# VibeMotors.net
KiCad netlist of a schematic drawn in EAGLE
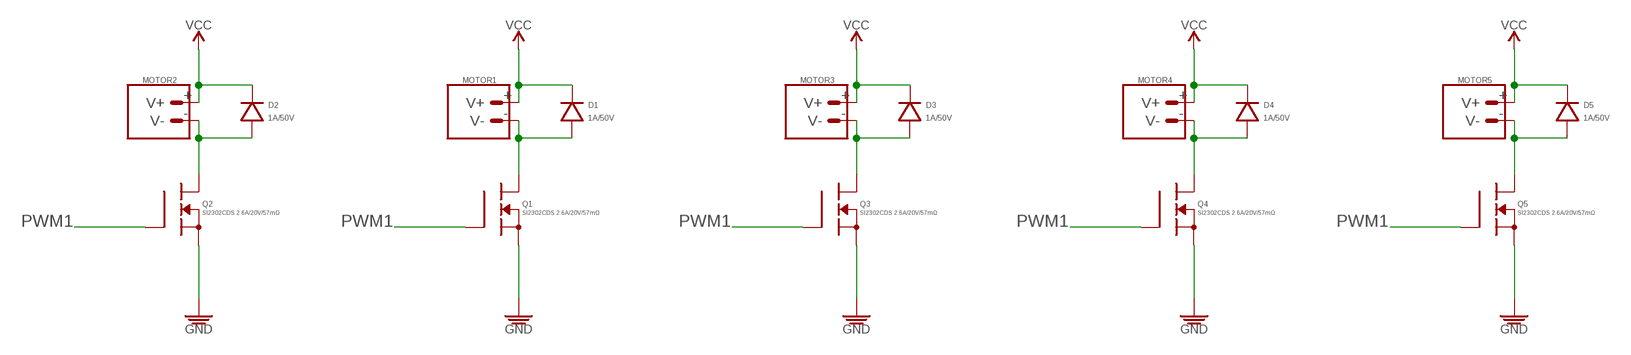
[diagram p0: schematic, sheet 1]

(export (version "E")
  (design (tool "Eeschema 10.0.6"))
  (components
    (comp (ref "D1")
      (value "1A/50V")
      (footprint "eagle-import:SOD123F")
      (fields
        (field (name "MFR") "Comchip Technology")
        (field (name "MPN") "CGRKM4001-HF")
        (field (name "CREATOR") "MrSwirlyEyes")
      )
      (libsource (lib "eagle-import") (part "DIODE_GENERAL-PURPOSE_SMD_GP_1A-50V"))
    )
    (comp (ref "D2")
      (value "1A/50V")
      (footprint "eagle-import:SOD123F")
      (fields
        (field (name "MFR") "Comchip Technology")
        (field (name "MPN") "CGRKM4001-HF")
        (field (name "CREATOR") "MrSwirlyEyes")
      )
      (libsource (lib "eagle-import") (part "DIODE_GENERAL-PURPOSE_SMD_GP_1A-50V"))
    )
    (comp (ref "D3")
      (value "1A/50V")
      (footprint "eagle-import:SOD123F")
      (fields
        (field (name "MFR") "Comchip Technology")
        (field (name "MPN") "CGRKM4001-HF")
        (field (name "CREATOR") "MrSwirlyEyes")
      )
      (libsource (lib "eagle-import") (part "DIODE_GENERAL-PURPOSE_SMD_GP_1A-50V"))
    )
    (comp (ref "D4")
      (value "1A/50V")
      (footprint "eagle-import:SOD123F")
      (fields
        (field (name "MFR") "Comchip Technology")
        (field (name "MPN") "CGRKM4001-HF")
        (field (name "CREATOR") "MrSwirlyEyes")
      )
      (libsource (lib "eagle-import") (part "DIODE_GENERAL-PURPOSE_SMD_GP_1A-50V"))
    )
    (comp (ref "D5")
      (value "1A/50V")
      (footprint "eagle-import:SOD123F")
      (fields
        (field (name "MFR") "Comchip Technology")
        (field (name "MPN") "CGRKM4001-HF")
        (field (name "CREATOR") "MrSwirlyEyes")
      )
      (libsource (lib "eagle-import") (part "DIODE_GENERAL-PURPOSE_SMD_GP_1A-50V"))
    )
    (comp (ref "MOTOR1")
      (value "MOTOR_PADSPTH")
      (footprint "eagle-import:CONNECTOR_MOTOR")
      (libsource (lib "eagle-import") (part "MOTOR_PADSPTH"))
    )
    (comp (ref "MOTOR2")
      (value "MOTOR_PADSPTH")
      (footprint "eagle-import:CONNECTOR_MOTOR")
      (libsource (lib "eagle-import") (part "MOTOR_PADSPTH"))
    )
    (comp (ref "MOTOR3")
      (value "MOTOR_PADSPTH")
      (footprint "eagle-import:CONNECTOR_MOTOR")
      (libsource (lib "eagle-import") (part "MOTOR_PADSPTH"))
    )
    (comp (ref "MOTOR4")
      (value "MOTOR_PADSPTH")
      (footprint "eagle-import:CONNECTOR_MOTOR")
      (libsource (lib "eagle-import") (part "MOTOR_PADSPTH"))
    )
    (comp (ref "MOTOR5")
      (value "MOTOR_PADSPTH")
      (footprint "eagle-import:CONNECTOR_MOTOR")
      (libsource (lib "eagle-import") (part "MOTOR_PADSPTH"))
    )
    (comp (ref "Q1")
      (value "SI2302CDS 2.6A/20V/57mΩ")
      (footprint "eagle-import:SOT23-3")
      (fields
        (field (name "MFR") "Vishay Siliconix")
        (field (name "MPN") "SI2302CDS-T1-GE3")
        (field (name "CREATOR") "MrSwirlyEyes")
      )
      (libsource (lib "eagle-import") (part "MOSFET_N-CHANNEL_SI2302CDS_2.6A-20V-0.057OHM"))
    )
    (comp (ref "Q2")
      (value "SI2302CDS 2.6A/20V/57mΩ")
      (footprint "eagle-import:SOT23-3")
      (fields
        (field (name "MFR") "Vishay Siliconix")
        (field (name "MPN") "SI2302CDS-T1-GE3")
        (field (name "CREATOR") "MrSwirlyEyes")
      )
      (libsource (lib "eagle-import") (part "MOSFET_N-CHANNEL_SI2302CDS_2.6A-20V-0.057OHM"))
    )
    (comp (ref "Q3")
      (value "SI2302CDS 2.6A/20V/57mΩ")
      (footprint "eagle-import:SOT23-3")
      (fields
        (field (name "MFR") "Vishay Siliconix")
        (field (name "MPN") "SI2302CDS-T1-GE3")
        (field (name "CREATOR") "MrSwirlyEyes")
      )
      (libsource (lib "eagle-import") (part "MOSFET_N-CHANNEL_SI2302CDS_2.6A-20V-0.057OHM"))
    )
    (comp (ref "Q4")
      (value "SI2302CDS 2.6A/20V/57mΩ")
      (footprint "eagle-import:SOT23-3")
      (fields
        (field (name "MFR") "Vishay Siliconix")
        (field (name "MPN") "SI2302CDS-T1-GE3")
        (field (name "CREATOR") "MrSwirlyEyes")
      )
      (libsource (lib "eagle-import") (part "MOSFET_N-CHANNEL_SI2302CDS_2.6A-20V-0.057OHM"))
    )
    (comp (ref "Q5")
      (value "SI2302CDS 2.6A/20V/57mΩ")
      (footprint "eagle-import:SOT23-3")
      (fields
        (field (name "MFR") "Vishay Siliconix")
        (field (name "MPN") "SI2302CDS-T1-GE3")
        (field (name "CREATOR") "MrSwirlyEyes")
      )
      (libsource (lib "eagle-import") (part "MOSFET_N-CHANNEL_SI2302CDS_2.6A-20V-0.057OHM"))
    )
  )
  (nets
    (net (code "1") (name "/PWM1") (class "Default")
      (node (ref "Q1") (pin "G") (pinfunction "G_G") (pintype "passive"))
      (node (ref "Q2") (pin "G") (pinfunction "G_G") (pintype "passive"))
      (node (ref "Q3") (pin "G") (pinfunction "G_G") (pintype "passive"))
      (node (ref "Q4") (pin "G") (pinfunction "G_G") (pintype "passive"))
      (node (ref "Q5") (pin "G") (pinfunction "G_G") (pintype "passive"))
    )
    (net (code "2") (name "GND") (class "Default")
      (node (ref "Q1") (pin "S") (pinfunction "S_S") (pintype "passive"))
      (node (ref "Q2") (pin "S") (pinfunction "S_S") (pintype "passive"))
      (node (ref "Q3") (pin "S") (pinfunction "S_S") (pintype "passive"))
      (node (ref "Q4") (pin "S") (pinfunction "S_S") (pintype "passive"))
      (node (ref "Q5") (pin "S") (pinfunction "S_S") (pintype "passive"))
    )
    (net (code "3") (name "Net-(MOTOR1-V-)") (class "Default")
      (node (ref "D1") (pin "A") (pinfunction "A_A") (pintype "passive"))
      (node (ref "MOTOR1") (pin "-") (pinfunction "V-_-") (pintype "bidirectional"))
      (node (ref "Q1") (pin "D") (pinfunction "D_D") (pintype "passive"))
    )
    (net (code "4") (name "Net-(MOTOR2-V-)") (class "Default")
      (node (ref "D2") (pin "A") (pinfunction "A_A") (pintype "passive"))
      (node (ref "MOTOR2") (pin "-") (pinfunction "V-_-") (pintype "bidirectional"))
      (node (ref "Q2") (pin "D") (pinfunction "D_D") (pintype "passive"))
    )
    (net (code "5") (name "Net-(MOTOR3-V-)") (class "Default")
      (node (ref "D3") (pin "A") (pinfunction "A_A") (pintype "passive"))
      (node (ref "MOTOR3") (pin "-") (pinfunction "V-_-") (pintype "bidirectional"))
      (node (ref "Q3") (pin "D") (pinfunction "D_D") (pintype "passive"))
    )
    (net (code "6") (name "Net-(MOTOR4-V-)") (class "Default")
      (node (ref "D4") (pin "A") (pinfunction "A_A") (pintype "passive"))
      (node (ref "MOTOR4") (pin "-") (pinfunction "V-_-") (pintype "bidirectional"))
      (node (ref "Q4") (pin "D") (pinfunction "D_D") (pintype "passive"))
    )
    (net (code "7") (name "Net-(MOTOR5-V-)") (class "Default")
      (node (ref "D5") (pin "A") (pinfunction "A_A") (pintype "passive"))
      (node (ref "MOTOR5") (pin "-") (pinfunction "V-_-") (pintype "bidirectional"))
      (node (ref "Q5") (pin "D") (pinfunction "D_D") (pintype "passive"))
    )
    (net (code "8") (name "VCC") (class "Default")
      (node (ref "D1") (pin "K") (pinfunction "K_K") (pintype "passive"))
      (node (ref "D2") (pin "K") (pinfunction "K_K") (pintype "passive"))
      (node (ref "D3") (pin "K") (pinfunction "K_K") (pintype "passive"))
      (node (ref "D4") (pin "K") (pinfunction "K_K") (pintype "passive"))
      (node (ref "D5") (pin "K") (pinfunction "K_K") (pintype "passive"))
      (node (ref "MOTOR1") (pin "+") (pinfunction "V+_+") (pintype "bidirectional"))
      (node (ref "MOTOR2") (pin "+") (pinfunction "V+_+") (pintype "bidirectional"))
      (node (ref "MOTOR3") (pin "+") (pinfunction "V+_+") (pintype "bidirectional"))
      (node (ref "MOTOR4") (pin "+") (pinfunction "V+_+") (pintype "bidirectional"))
      (node (ref "MOTOR5") (pin "+") (pinfunction "V+_+") (pintype "bidirectional"))
    )
  )
)
